# MCP23017_O8_v1_0.net
KiCad netlist of a schematic drawn in EAGLE
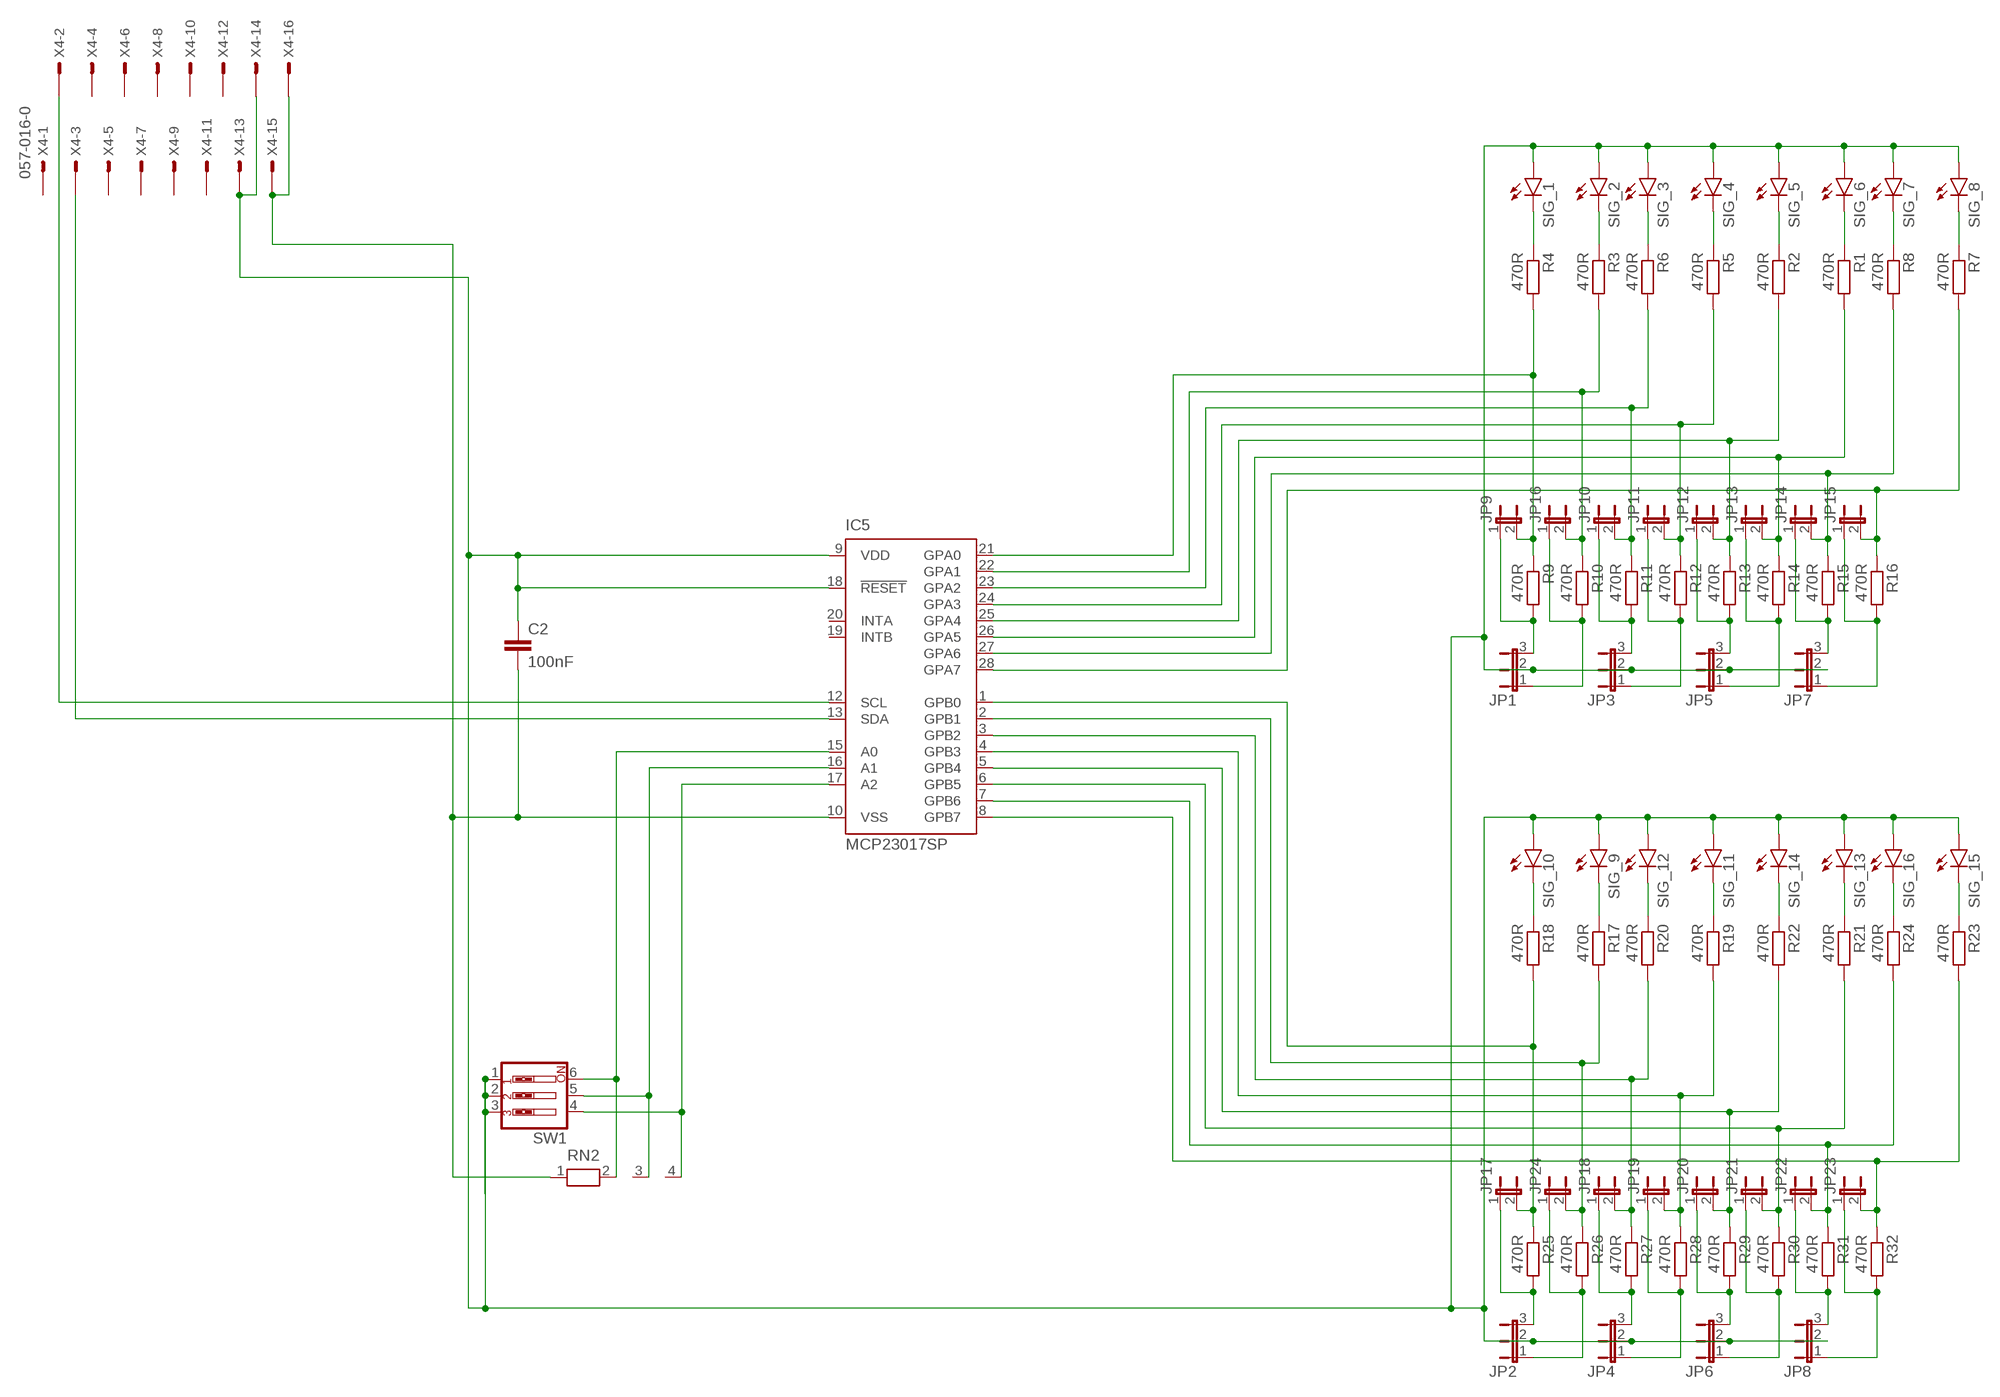
[diagram p0: schematic, sheet 1]

(export (version "E")
  (design (tool "Eeschema 10.0.6"))
  (components
    (comp (ref "C2")
      (value "100nF")
      (footprint "eagle-import:C025-024X044")
      (libsource (lib "eagle-import") (part "C-EU025-024X044"))
    )
    (comp (ref "IC5")
      (value "MCP23017SP")
      (footprint "eagle-import:DIL28-3")
      (libsource (lib "eagle-import") (part "MCP23017SP"))
    )
    (comp (ref "JP1")
      (value "JP2E")
      (footprint "eagle-import:JP2")
      (libsource (lib "eagle-import") (part "JP2E"))
    )
    (comp (ref "JP2")
      (value "JP2E")
      (footprint "eagle-import:JP2")
      (libsource (lib "eagle-import") (part "JP2E"))
    )
    (comp (ref "JP3")
      (value "JP2E")
      (footprint "eagle-import:JP2")
      (libsource (lib "eagle-import") (part "JP2E"))
    )
    (comp (ref "JP4")
      (value "JP2E")
      (footprint "eagle-import:JP2")
      (libsource (lib "eagle-import") (part "JP2E"))
    )
    (comp (ref "JP5")
      (value "JP2E")
      (footprint "eagle-import:JP2")
      (libsource (lib "eagle-import") (part "JP2E"))
    )
    (comp (ref "JP6")
      (value "JP2E")
      (footprint "eagle-import:JP2")
      (libsource (lib "eagle-import") (part "JP2E"))
    )
    (comp (ref "JP7")
      (value "JP2E")
      (footprint "eagle-import:JP2")
      (libsource (lib "eagle-import") (part "JP2E"))
    )
    (comp (ref "JP8")
      (value "JP2E")
      (footprint "eagle-import:JP2")
      (libsource (lib "eagle-import") (part "JP2E"))
    )
    (comp (ref "JP9")
      (value "JP1E")
      (footprint "eagle-import:JP1")
      (libsource (lib "eagle-import") (part "JP1E"))
    )
    (comp (ref "JP10")
      (value "JP1E")
      (footprint "eagle-import:JP1")
      (libsource (lib "eagle-import") (part "JP1E"))
    )
    (comp (ref "JP11")
      (value "JP1E")
      (footprint "eagle-import:JP1")
      (libsource (lib "eagle-import") (part "JP1E"))
    )
    (comp (ref "JP12")
      (value "JP1E")
      (footprint "eagle-import:JP1")
      (libsource (lib "eagle-import") (part "JP1E"))
    )
    (comp (ref "JP13")
      (value "JP1E")
      (footprint "eagle-import:JP1")
      (libsource (lib "eagle-import") (part "JP1E"))
    )
    (comp (ref "JP14")
      (value "JP1E")
      (footprint "eagle-import:JP1")
      (libsource (lib "eagle-import") (part "JP1E"))
    )
    (comp (ref "JP15")
      (value "JP1E")
      (footprint "eagle-import:JP1")
      (libsource (lib "eagle-import") (part "JP1E"))
    )
    (comp (ref "JP16")
      (value "JP1E")
      (footprint "eagle-import:JP1")
      (libsource (lib "eagle-import") (part "JP1E"))
    )
    (comp (ref "JP17")
      (value "JP1E")
      (footprint "eagle-import:JP1")
      (libsource (lib "eagle-import") (part "JP1E"))
    )
    (comp (ref "JP18")
      (value "JP1E")
      (footprint "eagle-import:JP1")
      (libsource (lib "eagle-import") (part "JP1E"))
    )
    (comp (ref "JP19")
      (value "JP1E")
      (footprint "eagle-import:JP1")
      (libsource (lib "eagle-import") (part "JP1E"))
    )
    (comp (ref "JP20")
      (value "JP1E")
      (footprint "eagle-import:JP1")
      (libsource (lib "eagle-import") (part "JP1E"))
    )
    (comp (ref "JP21")
      (value "JP1E")
      (footprint "eagle-import:JP1")
      (libsource (lib "eagle-import") (part "JP1E"))
    )
    (comp (ref "JP22")
      (value "JP1E")
      (footprint "eagle-import:JP1")
      (libsource (lib "eagle-import") (part "JP1E"))
    )
    (comp (ref "JP23")
      (value "JP1E")
      (footprint "eagle-import:JP1")
      (libsource (lib "eagle-import") (part "JP1E"))
    )
    (comp (ref "JP24")
      (value "JP1E")
      (footprint "eagle-import:JP1")
      (libsource (lib "eagle-import") (part "JP1E"))
    )
    (comp (ref "R1")
      (value "470R")
      (footprint "eagle-import:0309_10")
      (libsource (lib "eagle-import") (part "R-EU_0309/10"))
    )
    (comp (ref "R2")
      (value "470R")
      (footprint "eagle-import:0309_10")
      (libsource (lib "eagle-import") (part "R-EU_0309/10"))
    )
    (comp (ref "R3")
      (value "470R")
      (footprint "eagle-import:0309_10")
      (libsource (lib "eagle-import") (part "R-EU_0309/10"))
    )
    (comp (ref "R4")
      (value "470R")
      (footprint "eagle-import:0309_10")
      (libsource (lib "eagle-import") (part "R-EU_0309/10"))
    )
    (comp (ref "R5")
      (value "470R")
      (footprint "eagle-import:0309_10")
      (libsource (lib "eagle-import") (part "R-EU_0309/10"))
    )
    (comp (ref "R6")
      (value "470R")
      (footprint "eagle-import:0309_10")
      (libsource (lib "eagle-import") (part "R-EU_0309/10"))
    )
    (comp (ref "R7")
      (value "470R")
      (footprint "eagle-import:0309_10")
      (libsource (lib "eagle-import") (part "R-EU_0309/10"))
    )
    (comp (ref "R8")
      (value "470R")
      (footprint "eagle-import:0309_10")
      (libsource (lib "eagle-import") (part "R-EU_0309/10"))
    )
    (comp (ref "R9")
      (value "470R")
      (footprint "eagle-import:0309_10")
      (libsource (lib "eagle-import") (part "R-EU_0309/10"))
    )
    (comp (ref "R10")
      (value "470R")
      (footprint "eagle-import:0309_10")
      (libsource (lib "eagle-import") (part "R-EU_0309/10"))
    )
    (comp (ref "R11")
      (value "470R")
      (footprint "eagle-import:0309_10")
      (libsource (lib "eagle-import") (part "R-EU_0309/10"))
    )
    (comp (ref "R12")
      (value "470R")
      (footprint "eagle-import:0309_10")
      (libsource (lib "eagle-import") (part "R-EU_0309/10"))
    )
    (comp (ref "R13")
      (value "470R")
      (footprint "eagle-import:0309_10")
      (libsource (lib "eagle-import") (part "R-EU_0309/10"))
    )
    (comp (ref "R14")
      (value "470R")
      (footprint "eagle-import:0309_10")
      (libsource (lib "eagle-import") (part "R-EU_0309/10"))
    )
    (comp (ref "R15")
      (value "470R")
      (footprint "eagle-import:0309_10")
      (libsource (lib "eagle-import") (part "R-EU_0309/10"))
    )
    (comp (ref "R16")
      (value "470R")
      (footprint "eagle-import:0309_10")
      (libsource (lib "eagle-import") (part "R-EU_0309/10"))
    )
    (comp (ref "R17")
      (value "470R")
      (footprint "eagle-import:0309_10")
      (libsource (lib "eagle-import") (part "R-EU_0309/10"))
    )
    (comp (ref "R18")
      (value "470R")
      (footprint "eagle-import:0309_10")
      (libsource (lib "eagle-import") (part "R-EU_0309/10"))
    )
    (comp (ref "R19")
      (value "470R")
      (footprint "eagle-import:0309_10")
      (libsource (lib "eagle-import") (part "R-EU_0309/10"))
    )
    (comp (ref "R20")
      (value "470R")
      (footprint "eagle-import:0309_10")
      (libsource (lib "eagle-import") (part "R-EU_0309/10"))
    )
    (comp (ref "R21")
      (value "470R")
      (footprint "eagle-import:0309_10")
      (libsource (lib "eagle-import") (part "R-EU_0309/10"))
    )
    (comp (ref "R22")
      (value "470R")
      (footprint "eagle-import:0309_10")
      (libsource (lib "eagle-import") (part "R-EU_0309/10"))
    )
    (comp (ref "R23")
      (value "470R")
      (footprint "eagle-import:0309_10")
      (libsource (lib "eagle-import") (part "R-EU_0309/10"))
    )
    (comp (ref "R24")
      (value "470R")
      (footprint "eagle-import:0309_10")
      (libsource (lib "eagle-import") (part "R-EU_0309/10"))
    )
    (comp (ref "R25")
      (value "470R")
      (footprint "eagle-import:0309_10")
      (libsource (lib "eagle-import") (part "R-EU_0309/10"))
    )
    (comp (ref "R26")
      (value "470R")
      (footprint "eagle-import:0309_10")
      (libsource (lib "eagle-import") (part "R-EU_0309/10"))
    )
    (comp (ref "R27")
      (value "470R")
      (footprint "eagle-import:0309_10")
      (libsource (lib "eagle-import") (part "R-EU_0309/10"))
    )
    (comp (ref "R28")
      (value "470R")
      (footprint "eagle-import:0309_10")
      (libsource (lib "eagle-import") (part "R-EU_0309/10"))
    )
    (comp (ref "R29")
      (value "470R")
      (footprint "eagle-import:0309_10")
      (libsource (lib "eagle-import") (part "R-EU_0309/10"))
    )
    (comp (ref "R30")
      (value "470R")
      (footprint "eagle-import:0309_10")
      (libsource (lib "eagle-import") (part "R-EU_0309/10"))
    )
    (comp (ref "R31")
      (value "470R")
      (footprint "eagle-import:0309_10")
      (libsource (lib "eagle-import") (part "R-EU_0309/10"))
    )
    (comp (ref "R32")
      (value "470R")
      (footprint "eagle-import:0309_10")
      (libsource (lib "eagle-import") (part "R-EU_0309/10"))
    )
    (comp (ref "RN2")
      (value "RN03")
      (footprint "eagle-import:RN-3")
      (libsource (lib "eagle-import") (part "RN03"))
    )
    (comp (ref "SIG_1")
      (value "LED3MM")
      (footprint "eagle-import:LED3MM")
      (libsource (lib "eagle-import") (part "LED3MM"))
    )
    (comp (ref "SIG_2")
      (value "LED3MM")
      (footprint "eagle-import:LED3MM")
      (libsource (lib "eagle-import") (part "LED3MM"))
    )
    (comp (ref "SIG_3")
      (value "LED3MM")
      (footprint "eagle-import:LED3MM")
      (libsource (lib "eagle-import") (part "LED3MM"))
    )
    (comp (ref "SIG_4")
      (value "LED3MM")
      (footprint "eagle-import:LED3MM")
      (libsource (lib "eagle-import") (part "LED3MM"))
    )
    (comp (ref "SIG_5")
      (value "LED3MM")
      (footprint "eagle-import:LED3MM")
      (libsource (lib "eagle-import") (part "LED3MM"))
    )
    (comp (ref "SIG_6")
      (value "LED3MM")
      (footprint "eagle-import:LED3MM")
      (libsource (lib "eagle-import") (part "LED3MM"))
    )
    (comp (ref "SIG_7")
      (value "LED3MM")
      (footprint "eagle-import:LED3MM")
      (libsource (lib "eagle-import") (part "LED3MM"))
    )
    (comp (ref "SIG_8")
      (value "LED3MM")
      (footprint "eagle-import:LED3MM")
      (libsource (lib "eagle-import") (part "LED3MM"))
    )
    (comp (ref "SIG_9")
      (value "LED3MM")
      (footprint "eagle-import:LED3MM")
      (libsource (lib "eagle-import") (part "LED3MM"))
    )
    (comp (ref "SIG_10")
      (value "LED3MM")
      (footprint "eagle-import:LED3MM")
      (libsource (lib "eagle-import") (part "LED3MM"))
    )
    (comp (ref "SIG_11")
      (value "LED3MM")
      (footprint "eagle-import:LED3MM")
      (libsource (lib "eagle-import") (part "LED3MM"))
    )
    (comp (ref "SIG_12")
      (value "LED3MM")
      (footprint "eagle-import:LED3MM")
      (libsource (lib "eagle-import") (part "LED3MM"))
    )
    (comp (ref "SIG_13")
      (value "LED3MM")
      (footprint "eagle-import:LED3MM")
      (libsource (lib "eagle-import") (part "LED3MM"))
    )
    (comp (ref "SIG_14")
      (value "LED3MM")
      (footprint "eagle-import:LED3MM")
      (libsource (lib "eagle-import") (part "LED3MM"))
    )
    (comp (ref "SIG_15")
      (value "LED3MM")
      (footprint "eagle-import:LED3MM")
      (libsource (lib "eagle-import") (part "LED3MM"))
    )
    (comp (ref "SIG_16")
      (value "LED3MM")
      (footprint "eagle-import:LED3MM")
      (libsource (lib "eagle-import") (part "LED3MM"))
    )
    (comp (ref "SW1")
      (value "SW_DIP-3")
      (footprint "eagle-import:EDG-03")
      (libsource (lib "eagle-import") (part "SW_DIP-3"))
    )
    (comp (ref "X4")
      (value "057-016-0")
      (footprint "eagle-import:057-016-0")
      (libsource (lib "eagle-import") (part "057-016-0"))
    )
  )
  (nets
    (net (code "1") (name "Net-(IC5-A0)") (class "Default")
      (node (ref "IC5") (pin "15") (pinfunction "A0_15") (pintype "input"))
      (node (ref "RN2") (pin "2") (pinfunction "2_2") (pintype "passive"))
      (node (ref "SW1") (pin "6") (pinfunction "6_6") (pintype "passive"))
    )
    (net (code "2") (name "Net-(IC5-A1)") (class "Default")
      (node (ref "IC5") (pin "16") (pinfunction "A1_16") (pintype "input"))
      (node (ref "RN2") (pin "3") (pinfunction "3_3") (pintype "passive"))
      (node (ref "SW1") (pin "5") (pinfunction "5_5") (pintype "passive"))
    )
    (net (code "3") (name "Net-(IC5-A2)") (class "Default")
      (node (ref "IC5") (pin "17") (pinfunction "A2_17") (pintype "input"))
      (node (ref "RN2") (pin "4") (pinfunction "4_4") (pintype "passive"))
      (node (ref "SW1") (pin "4") (pinfunction "4_4") (pintype "passive"))
    )
    (net (code "4") (name "Net-(IC5-GPA0)") (class "Default")
      (node (ref "IC5") (pin "21") (pinfunction "GPA0_21") (pintype "bidirectional"))
      (node (ref "JP9") (pin "2") (pinfunction "2_2") (pintype "passive"))
      (node (ref "R4") (pin "2") (pinfunction "2_2") (pintype "passive"))
      (node (ref "R9") (pin "1") (pinfunction "1_1") (pintype "passive"))
    )
    (net (code "5") (name "Net-(IC5-GPA1)") (class "Default")
      (node (ref "IC5") (pin "22") (pinfunction "GPA1_22") (pintype "bidirectional"))
      (node (ref "JP16") (pin "2") (pinfunction "2_2") (pintype "passive"))
      (node (ref "R10") (pin "1") (pinfunction "1_1") (pintype "passive"))
      (node (ref "R3") (pin "2") (pinfunction "2_2") (pintype "passive"))
    )
    (net (code "6") (name "Net-(IC5-GPA2)") (class "Default")
      (node (ref "IC5") (pin "23") (pinfunction "GPA2_23") (pintype "bidirectional"))
      (node (ref "JP10") (pin "2") (pinfunction "2_2") (pintype "passive"))
      (node (ref "R11") (pin "1") (pinfunction "1_1") (pintype "passive"))
      (node (ref "R6") (pin "2") (pinfunction "2_2") (pintype "passive"))
    )
    (net (code "7") (name "Net-(IC5-GPA3)") (class "Default")
      (node (ref "IC5") (pin "24") (pinfunction "GPA3_24") (pintype "bidirectional"))
      (node (ref "JP11") (pin "2") (pinfunction "2_2") (pintype "passive"))
      (node (ref "R12") (pin "1") (pinfunction "1_1") (pintype "passive"))
      (node (ref "R5") (pin "2") (pinfunction "2_2") (pintype "passive"))
    )
    (net (code "8") (name "Net-(IC5-GPA4)") (class "Default")
      (node (ref "IC5") (pin "25") (pinfunction "GPA4_25") (pintype "bidirectional"))
      (node (ref "JP12") (pin "2") (pinfunction "2_2") (pintype "passive"))
      (node (ref "R13") (pin "1") (pinfunction "1_1") (pintype "passive"))
      (node (ref "R2") (pin "2") (pinfunction "2_2") (pintype "passive"))
    )
    (net (code "9") (name "Net-(IC5-GPA5)") (class "Default")
      (node (ref "IC5") (pin "26") (pinfunction "GPA5_26") (pintype "bidirectional"))
      (node (ref "JP13") (pin "2") (pinfunction "2_2") (pintype "passive"))
      (node (ref "R1") (pin "2") (pinfunction "2_2") (pintype "passive"))
      (node (ref "R14") (pin "1") (pinfunction "1_1") (pintype "passive"))
    )
    (net (code "10") (name "Net-(IC5-GPA6)") (class "Default")
      (node (ref "IC5") (pin "27") (pinfunction "GPA6_27") (pintype "bidirectional"))
      (node (ref "JP14") (pin "2") (pinfunction "2_2") (pintype "passive"))
      (node (ref "R15") (pin "1") (pinfunction "1_1") (pintype "passive"))
      (node (ref "R8") (pin "2") (pinfunction "2_2") (pintype "passive"))
    )
    (net (code "11") (name "Net-(IC5-GPA7)") (class "Default")
      (node (ref "IC5") (pin "28") (pinfunction "GPA7_28") (pintype "bidirectional"))
      (node (ref "JP15") (pin "2") (pinfunction "2_2") (pintype "passive"))
      (node (ref "R16") (pin "1") (pinfunction "1_1") (pintype "passive"))
      (node (ref "R7") (pin "2") (pinfunction "2_2") (pintype "passive"))
    )
    (net (code "12") (name "Net-(IC5-GPB0)") (class "Default")
      (node (ref "IC5") (pin "1") (pinfunction "GPB0_1") (pintype "bidirectional"))
      (node (ref "JP17") (pin "2") (pinfunction "2_2") (pintype "passive"))
      (node (ref "R18") (pin "2") (pinfunction "2_2") (pintype "passive"))
      (node (ref "R25") (pin "1") (pinfunction "1_1") (pintype "passive"))
    )
    (net (code "13") (name "Net-(IC5-GPB1)") (class "Default")
      (node (ref "IC5") (pin "2") (pinfunction "GPB1_2") (pintype "bidirectional"))
      (node (ref "JP24") (pin "2") (pinfunction "2_2") (pintype "passive"))
      (node (ref "R17") (pin "2") (pinfunction "2_2") (pintype "passive"))
      (node (ref "R26") (pin "1") (pinfunction "1_1") (pintype "passive"))
    )
    (net (code "14") (name "Net-(IC5-GPB2)") (class "Default")
      (node (ref "IC5") (pin "3") (pinfunction "GPB2_3") (pintype "bidirectional"))
      (node (ref "JP18") (pin "2") (pinfunction "2_2") (pintype "passive"))
      (node (ref "R20") (pin "2") (pinfunction "2_2") (pintype "passive"))
      (node (ref "R27") (pin "1") (pinfunction "1_1") (pintype "passive"))
    )
    (net (code "15") (name "Net-(IC5-GPB3)") (class "Default")
      (node (ref "IC5") (pin "4") (pinfunction "GPB3_4") (pintype "bidirectional"))
      (node (ref "JP19") (pin "2") (pinfunction "2_2") (pintype "passive"))
      (node (ref "R19") (pin "2") (pinfunction "2_2") (pintype "passive"))
      (node (ref "R28") (pin "1") (pinfunction "1_1") (pintype "passive"))
    )
    (net (code "16") (name "Net-(IC5-GPB4)") (class "Default")
      (node (ref "IC5") (pin "5") (pinfunction "GPB4_5") (pintype "bidirectional"))
      (node (ref "JP20") (pin "2") (pinfunction "2_2") (pintype "passive"))
      (node (ref "R22") (pin "2") (pinfunction "2_2") (pintype "passive"))
      (node (ref "R29") (pin "1") (pinfunction "1_1") (pintype "passive"))
    )
    (net (code "17") (name "Net-(IC5-GPB5)") (class "Default")
      (node (ref "IC5") (pin "6") (pinfunction "GPB5_6") (pintype "bidirectional"))
      (node (ref "JP21") (pin "2") (pinfunction "2_2") (pintype "passive"))
      (node (ref "R21") (pin "2") (pinfunction "2_2") (pintype "passive"))
      (node (ref "R30") (pin "1") (pinfunction "1_1") (pintype "passive"))
    )
    (net (code "18") (name "Net-(IC5-GPB6)") (class "Default")
      (node (ref "IC5") (pin "7") (pinfunction "GPB6_7") (pintype "bidirectional"))
      (node (ref "JP22") (pin "2") (pinfunction "2_2") (pintype "passive"))
      (node (ref "R24") (pin "2") (pinfunction "2_2") (pintype "passive"))
      (node (ref "R31") (pin "1") (pinfunction "1_1") (pintype "passive"))
    )
    (net (code "19") (name "Net-(IC5-GPB7)") (class "Default")
      (node (ref "IC5") (pin "8") (pinfunction "GPB7_8") (pintype "bidirectional"))
      (node (ref "JP23") (pin "2") (pinfunction "2_2") (pintype "passive"))
      (node (ref "R23") (pin "2") (pinfunction "2_2") (pintype "passive"))
      (node (ref "R32") (pin "1") (pinfunction "1_1") (pintype "passive"))
    )
    (net (code "20") (name "Net-(IC5-SCL)") (class "Default")
      (node (ref "IC5") (pin "12") (pinfunction "SCL_12") (pintype "input"))
      (node (ref "X4") (pin "2") (pinfunction "S_2") (pintype "passive"))
    )
    (net (code "21") (name "Net-(IC5-SDA)") (class "Default")
      (node (ref "IC5") (pin "13") (pinfunction "SDA_13") (pintype "bidirectional"))
      (node (ref "X4") (pin "3") (pinfunction "S_3") (pintype "passive"))
    )
    (net (code "22") (name "Net-(IC5-VDD)") (class "Default")
      (node (ref "C2") (pin "1") (pinfunction "1_1") (pintype "passive"))
      (node (ref "IC5") (pin "18") (pinfunction "~{RESET}_18") (pintype "input"))
      (node (ref "IC5") (pin "9") (pinfunction "VDD_9") (pintype "power_in"))
      (node (ref "JP1") (pin "2") (pinfunction "2_2") (pintype "passive"))
      (node (ref "JP2") (pin "2") (pinfunction "2_2") (pintype "passive"))
      (node (ref "JP3") (pin "2") (pinfunction "2_2") (pintype "passive"))
      (node (ref "JP4") (pin "2") (pinfunction "2_2") (pintype "passive"))
      (node (ref "JP5") (pin "2") (pinfunction "2_2") (pintype "passive"))
      (node (ref "JP6") (pin "2") (pinfunction "2_2") (pintype "passive"))
      (node (ref "JP7") (pin "2") (pinfunction "2_2") (pintype "passive"))
      (node (ref "JP8") (pin "2") (pinfunction "2_2") (pintype "passive"))
      (node (ref "SIG_1") (pin "A") (pinfunction "A_A") (pintype "passive"))
      (node (ref "SIG_10") (pin "A") (pinfunction "A_A") (pintype "passive"))
      (node (ref "SIG_11") (pin "A") (pinfunction "A_A") (pintype "passive"))
      (node (ref "SIG_12") (pin "A") (pinfunction "A_A") (pintype "passive"))
      (node (ref "SIG_13") (pin "A") (pinfunction "A_A") (pintype "passive"))
      (node (ref "SIG_14") (pin "A") (pinfunction "A_A") (pintype "passive"))
      (node (ref "SIG_15") (pin "A") (pinfunction "A_A") (pintype "passive"))
      (node (ref "SIG_16") (pin "A") (pinfunction "A_A") (pintype "passive"))
      (node (ref "SIG_2") (pin "A") (pinfunction "A_A") (pintype "passive"))
      (node (ref "SIG_3") (pin "A") (pinfunction "A_A") (pintype "passive"))
      (node (ref "SIG_4") (pin "A") (pinfunction "A_A") (pintype "passive"))
      (node (ref "SIG_5") (pin "A") (pinfunction "A_A") (pintype "passive"))
      (node (ref "SIG_6") (pin "A") (pinfunction "A_A") (pintype "passive"))
      (node (ref "SIG_7") (pin "A") (pinfunction "A_A") (pintype "passive"))
      (node (ref "SIG_8") (pin "A") (pinfunction "A_A") (pintype "passive"))
      (node (ref "SIG_9") (pin "A") (pinfunction "A_A") (pintype "passive"))
      (node (ref "SW1") (pin "1") (pinfunction "1_1") (pintype "passive"))
      (node (ref "SW1") (pin "2") (pinfunction "2_2") (pintype "passive"))
      (node (ref "SW1") (pin "3") (pinfunction "3_3") (pintype "passive"))
      (node (ref "X4") (pin "13") (pinfunction "S_13") (pintype "passive"))
      (node (ref "X4") (pin "14") (pinfunction "S_14") (pintype "passive"))
    )
    (net (code "23") (name "Net-(IC5-VSS)") (class "Default")
      (node (ref "C2") (pin "2") (pinfunction "2_2") (pintype "passive"))
      (node (ref "IC5") (pin "10") (pinfunction "VSS_10") (pintype "power_in"))
      (node (ref "RN2") (pin "1") (pinfunction "1_1") (pintype "passive"))
      (node (ref "X4") (pin "15") (pinfunction "S_15") (pintype "passive"))
      (node (ref "X4") (pin "16") (pinfunction "S_16") (pintype "passive"))
    )
    (net (code "24") (name "Net-(JP1-Pad1)") (class "Default")
      (node (ref "JP1") (pin "1") (pinfunction "1_1") (pintype "passive"))
      (node (ref "JP16") (pin "1") (pinfunction "1_1") (pintype "passive"))
      (node (ref "R10") (pin "2") (pinfunction "2_2") (pintype "passive"))
    )
    (net (code "25") (name "Net-(JP1-Pad3)") (class "Default")
      (node (ref "JP1") (pin "3") (pinfunction "3_3") (pintype "passive"))
      (node (ref "JP9") (pin "1") (pinfunction "1_1") (pintype "passive"))
      (node (ref "R9") (pin "2") (pinfunction "2_2") (pintype "passive"))
    )
    (net (code "26") (name "Net-(JP2-Pad1)") (class "Default")
      (node (ref "JP2") (pin "1") (pinfunction "1_1") (pintype "passive"))
      (node (ref "JP24") (pin "1") (pinfunction "1_1") (pintype "passive"))
      (node (ref "R26") (pin "2") (pinfunction "2_2") (pintype "passive"))
    )
    (net (code "27") (name "Net-(JP10-Pad1)") (class "Default")
      (node (ref "JP10") (pin "1") (pinfunction "1_1") (pintype "passive"))
      (node (ref "JP3") (pin "3") (pinfunction "3_3") (pintype "passive"))
      (node (ref "R11") (pin "2") (pinfunction "2_2") (pintype "passive"))
    )
    (net (code "28") (name "Net-(JP11-Pad1)") (class "Default")
      (node (ref "JP11") (pin "1") (pinfunction "1_1") (pintype "passive"))
      (node (ref "JP3") (pin "1") (pinfunction "1_1") (pintype "passive"))
      (node (ref "R12") (pin "2") (pinfunction "2_2") (pintype "passive"))
    )
    (net (code "29") (name "Net-(JP12-Pad1)") (class "Default")
      (node (ref "JP12") (pin "1") (pinfunction "1_1") (pintype "passive"))
      (node (ref "JP5") (pin "3") (pinfunction "3_3") (pintype "passive"))
      (node (ref "R13") (pin "2") (pinfunction "2_2") (pintype "passive"))
    )
    (net (code "30") (name "Net-(JP13-Pad1)") (class "Default")
      (node (ref "JP13") (pin "1") (pinfunction "1_1") (pintype "passive"))
      (node (ref "JP5") (pin "1") (pinfunction "1_1") (pintype "passive"))
      (node (ref "R14") (pin "2") (pinfunction "2_2") (pintype "passive"))
    )
    (net (code "31") (name "Net-(JP14-Pad1)") (class "Default")
      (node (ref "JP14") (pin "1") (pinfunction "1_1") (pintype "passive"))
      (node (ref "JP7") (pin "3") (pinfunction "3_3") (pintype "passive"))
      (node (ref "R15") (pin "2") (pinfunction "2_2") (pintype "passive"))
    )
    (net (code "32") (name "Net-(JP15-Pad1)") (class "Default")
      (node (ref "JP15") (pin "1") (pinfunction "1_1") (pintype "passive"))
      (node (ref "JP7") (pin "1") (pinfunction "1_1") (pintype "passive"))
      (node (ref "R16") (pin "2") (pinfunction "2_2") (pintype "passive"))
    )
    (net (code "33") (name "Net-(JP17-Pad1)") (class "Default")
      (node (ref "JP17") (pin "1") (pinfunction "1_1") (pintype "passive"))
      (node (ref "JP2") (pin "3") (pinfunction "3_3") (pintype "passive"))
      (node (ref "R25") (pin "2") (pinfunction "2_2") (pintype "passive"))
    )
    (net (code "34") (name "Net-(JP18-Pad1)") (class "Default")
      (node (ref "JP18") (pin "1") (pinfunction "1_1") (pintype "passive"))
      (node (ref "JP4") (pin "3") (pinfunction "3_3") (pintype "passive"))
      (node (ref "R27") (pin "2") (pinfunction "2_2") (pintype "passive"))
    )
    (net (code "35") (name "Net-(JP19-Pad1)") (class "Default")
      (node (ref "JP19") (pin "1") (pinfunction "1_1") (pintype "passive"))
      (node (ref "JP4") (pin "1") (pinfunction "1_1") (pintype "passive"))
      (node (ref "R28") (pin "2") (pinfunction "2_2") (pintype "passive"))
    )
    (net (code "36") (name "Net-(JP20-Pad1)") (class "Default")
      (node (ref "JP20") (pin "1") (pinfunction "1_1") (pintype "passive"))
      (node (ref "JP6") (pin "3") (pinfunction "3_3") (pintype "passive"))
      (node (ref "R29") (pin "2") (pinfunction "2_2") (pintype "passive"))
    )
    (net (code "37") (name "Net-(JP21-Pad1)") (class "Default")
      (node (ref "JP21") (pin "1") (pinfunction "1_1") (pintype "passive"))
      (node (ref "JP6") (pin "1") (pinfunction "1_1") (pintype "passive"))
      (node (ref "R30") (pin "2") (pinfunction "2_2") (pintype "passive"))
    )
    (net (code "38") (name "Net-(JP22-Pad1)") (class "Default")
      (node (ref "JP22") (pin "1") (pinfunction "1_1") (pintype "passive"))
      (node (ref "JP8") (pin "3") (pinfunction "3_3") (pintype "passive"))
      (node (ref "R31") (pin "2") (pinfunction "2_2") (pintype "passive"))
    )
    (net (code "39") (name "Net-(JP23-Pad1)") (class "Default")
      (node (ref "JP23") (pin "1") (pinfunction "1_1") (pintype "passive"))
      (node (ref "JP8") (pin "1") (pinfunction "1_1") (pintype "passive"))
      (node (ref "R32") (pin "2") (pinfunction "2_2") (pintype "passive"))
    )
    (net (code "40") (name "Net-(SIG_1-C)") (class "Default")
      (node (ref "R4") (pin "1") (pinfunction "1_1") (pintype "passive"))
      (node (ref "SIG_1") (pin "K") (pinfunction "C_K") (pintype "passive"))
    )
    (net (code "41") (name "Net-(SIG_2-C)") (class "Default")
      (node (ref "R3") (pin "1") (pinfunction "1_1") (pintype "passive"))
      (node (ref "SIG_2") (pin "K") (pinfunction "C_K") (pintype "passive"))
    )
    (net (code "42") (name "Net-(SIG_3-C)") (class "Default")
      (node (ref "R6") (pin "1") (pinfunction "1_1") (pintype "passive"))
      (node (ref "SIG_3") (pin "K") (pinfunction "C_K") (pintype "passive"))
    )
    (net (code "43") (name "Net-(SIG_4-C)") (class "Default")
      (node (ref "R5") (pin "1") (pinfunction "1_1") (pintype "passive"))
      (node (ref "SIG_4") (pin "K") (pinfunction "C_K") (pintype "passive"))
    )
    (net (code "44") (name "Net-(SIG_5-C)") (class "Default")
      (node (ref "R2") (pin "1") (pinfunction "1_1") (pintype "passive"))
      (node (ref "SIG_5") (pin "K") (pinfunction "C_K") (pintype "passive"))
    )
    (net (code "45") (name "Net-(SIG_6-C)") (class "Default")
      (node (ref "R1") (pin "1") (pinfunction "1_1") (pintype "passive"))
      (node (ref "SIG_6") (pin "K") (pinfunction "C_K") (pintype "passive"))
    )
    (net (code "46") (name "Net-(SIG_7-C)") (class "Default")
      (node (ref "R8") (pin "1") (pinfunction "1_1") (pintype "passive"))
      (node (ref "SIG_7") (pin "K") (pinfunction "C_K") (pintype "passive"))
    )
    (net (code "47") (name "Net-(SIG_8-C)") (class "Default")
      (node (ref "R7") (pin "1") (pinfunction "1_1") (pintype "passive"))
      (node (ref "SIG_8") (pin "K") (pinfunction "C_K") (pintype "passive"))
    )
    (net (code "48") (name "Net-(SIG_9-C)") (class "Default")
      (node (ref "R17") (pin "1") (pinfunction "1_1") (pintype "passive"))
      (node (ref "SIG_9") (pin "K") (pinfunction "C_K") (pintype "passive"))
    )
    (net (code "49") (name "Net-(SIG_10-C)") (class "Default")
      (node (ref "R18") (pin "1") (pinfunction "1_1") (pintype "passive"))
      (node (ref "SIG_10") (pin "K") (pinfunction "C_K") (pintype "passive"))
    )
    (net (code "50") (name "Net-(SIG_11-C)") (class "Default")
      (node (ref "R19") (pin "1") (pinfunction "1_1") (pintype "passive"))
      (node (ref "SIG_11") (pin "K") (pinfunction "C_K") (pintype "passive"))
    )
    (net (code "51") (name "Net-(SIG_12-C)") (class "Default")
      (node (ref "R20") (pin "1") (pinfunction "1_1") (pintype "passive"))
      (node (ref "SIG_12") (pin "K") (pinfunction "C_K") (pintype "passive"))
    )
    (net (code "52") (name "Net-(SIG_13-C)") (class "Default")
      (node (ref "R21") (pin "1") (pinfunction "1_1") (pintype "passive"))
      (node (ref "SIG_13") (pin "K") (pinfunction "C_K") (pintype "passive"))
    )
    (net (code "53") (name "Net-(SIG_14-C)") (class "Default")
      (node (ref "R22") (pin "1") (pinfunction "1_1") (pintype "passive"))
      (node (ref "SIG_14") (pin "K") (pinfunction "C_K") (pintype "passive"))
    )
    (net (code "54") (name "Net-(SIG_15-C)") (class "Default")
      (node (ref "R23") (pin "1") (pinfunction "1_1") (pintype "passive"))
      (node (ref "SIG_15") (pin "K") (pinfunction "C_K") (pintype "passive"))
    )
    (net (code "55") (name "Net-(SIG_16-C)") (class "Default")
      (node (ref "R24") (pin "1") (pinfunction "1_1") (pintype "passive"))
      (node (ref "SIG_16") (pin "K") (pinfunction "C_K") (pintype "passive"))
    )
    (net (code "56") (name "unconnected-(IC5-INTA-Pad20)") (class "Default")
      (node (ref "IC5") (pin "20") (pinfunction "INTA_20") (pintype "output"))
    )
    (net (code "57") (name "unconnected-(IC5-INTB-Pad19)") (class "Default")
      (node (ref "IC5") (pin "19") (pinfunction "INTB_19") (pintype "output"))
    )
    (net (code "58") (name "unconnected-(X4A-S-Pad1)") (class "Default")
      (node (ref "X4") (pin "1") (pinfunction "S_1") (pintype "passive"))
    )
    (net (code "59") (name "unconnected-(X4B-S-Pad10)") (class "Default")
      (node (ref "X4") (pin "10") (pinfunction "S_10") (pintype "passive"))
    )
    (net (code "60") (name "unconnected-(X4C-S-Pad11)") (class "Default")
      (node (ref "X4") (pin "11") (pinfunction "S_11") (pintype "passive"))
    )
    (net (code "61") (name "unconnected-(X4D-S-Pad12)") (class "Default")
      (node (ref "X4") (pin "12") (pinfunction "S_12") (pintype "passive"))
    )
    (net (code "62") (name "unconnected-(X4K-S-Pad4)") (class "Default")
      (node (ref "X4") (pin "4") (pinfunction "S_4") (pintype "passive"))
    )
    (net (code "63") (name "unconnected-(X4L-S-Pad5)") (class "Default")
      (node (ref "X4") (pin "5") (pinfunction "S_5") (pintype "passive"))
    )
    (net (code "64") (name "unconnected-(X4M-S-Pad6)") (class "Default")
      (node (ref "X4") (pin "6") (pinfunction "S_6") (pintype "passive"))
    )
    (net (code "65") (name "unconnected-(X4N-S-Pad7)") (class "Default")
      (node (ref "X4") (pin "7") (pinfunction "S_7") (pintype "passive"))
    )
    (net (code "66") (name "unconnected-(X4O-S-Pad8)") (class "Default")
      (node (ref "X4") (pin "8") (pinfunction "S_8") (pintype "passive"))
    )
    (net (code "67") (name "unconnected-(X4P-S-Pad9)") (class "Default")
      (node (ref "X4") (pin "9") (pinfunction "S_9") (pintype "passive"))
    )
  )
)
